# led-test.net
KiCad netlist of a schematic drawn in EAGLE
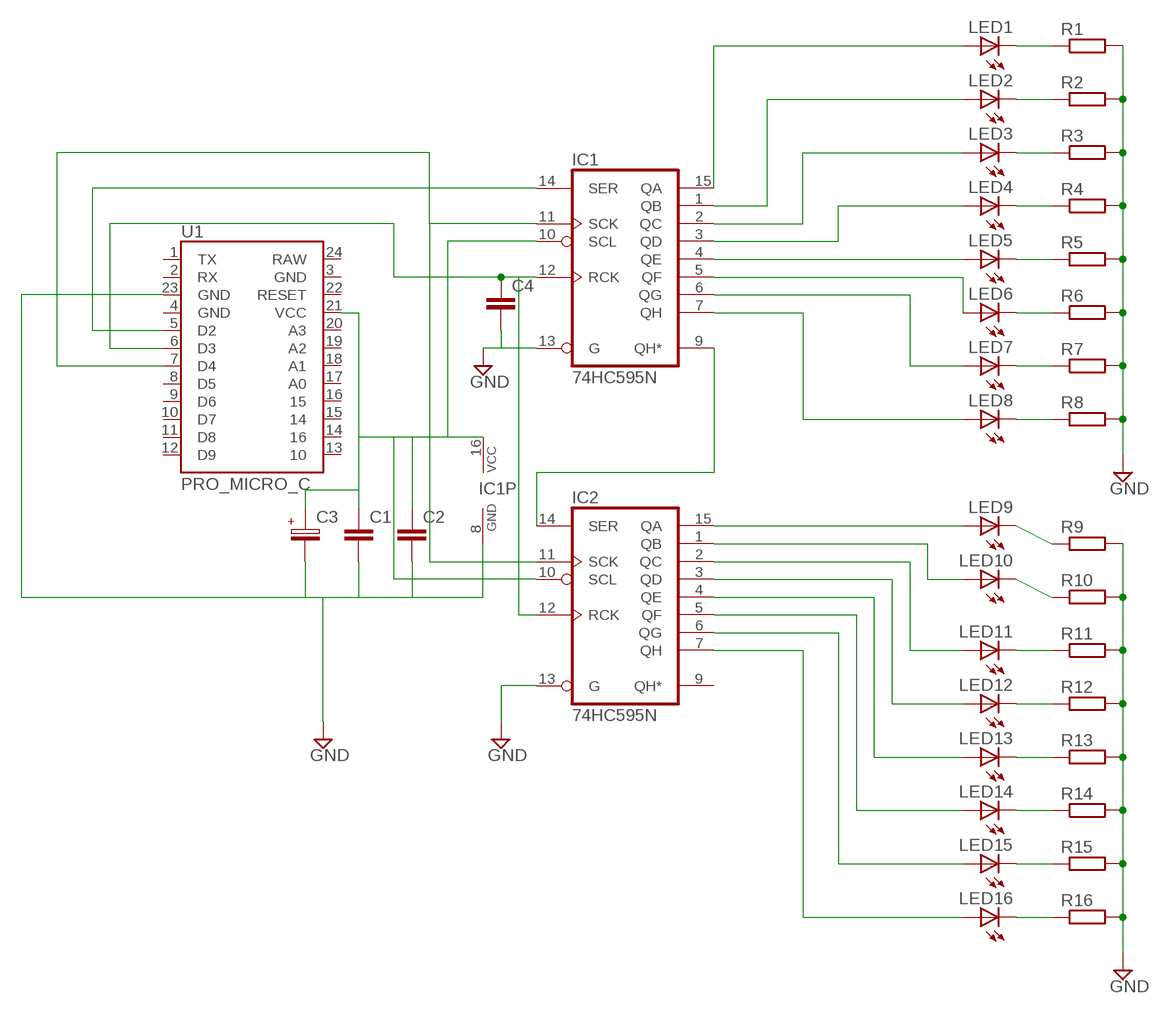
[diagram p0: schematic, sheet 1]

(export (version "E")
  (design (tool "Eeschema 10.0.6"))
  (components
    (comp (ref "C1")
      (value "072X0252")
      (footprint "eagle-import:072X025")
      (libsource (lib "eagle-import") (part "072X0252"))
    )
    (comp (ref "C2")
      (value "072X0252")
      (footprint "eagle-import:072X025")
      (libsource (lib "eagle-import") (part "072X0252"))
    )
    (comp (ref "C3")
      (value "050-EU")
      (footprint "eagle-import:050_020")
      (libsource (lib "eagle-import") (part "050-EU"))
    )
    (comp (ref "C4")
      (value "072X0252")
      (footprint "eagle-import:072X025")
      (libsource (lib "eagle-import") (part "072X0252"))
    )
    (comp (ref "IC1")
      (value "74HC595N")
      (footprint "eagle-import:DIL16")
      (libsource (lib "eagle-import") (part "74595NHC"))
    )
    (comp (ref "IC2")
      (value "74HC595N")
      (footprint "eagle-import:DIL16")
      (libsource (lib "eagle-import") (part "74595NHC"))
    )
    (comp (ref "LED1")
      (value "LED")
      (footprint "eagle-import:SMARTLED-TTW")
      (libsource (lib "eagle-import") (part "LED"))
    )
    (comp (ref "LED2")
      (value "LED")
      (footprint "eagle-import:SMARTLED-TTW")
      (libsource (lib "eagle-import") (part "LED"))
    )
    (comp (ref "LED3")
      (value "LED")
      (footprint "eagle-import:SMARTLED-TTW")
      (libsource (lib "eagle-import") (part "LED"))
    )
    (comp (ref "LED4")
      (value "LED")
      (footprint "eagle-import:SMARTLED-TTW")
      (libsource (lib "eagle-import") (part "LED"))
    )
    (comp (ref "LED5")
      (value "LED")
      (footprint "eagle-import:SMARTLED-TTW")
      (libsource (lib "eagle-import") (part "LED"))
    )
    (comp (ref "LED6")
      (value "LED")
      (footprint "eagle-import:SMARTLED-TTW")
      (libsource (lib "eagle-import") (part "LED"))
    )
    (comp (ref "LED7")
      (value "LED")
      (footprint "eagle-import:SMARTLED-TTW")
      (libsource (lib "eagle-import") (part "LED"))
    )
    (comp (ref "LED8")
      (value "LED")
      (footprint "eagle-import:SMARTLED-TTW")
      (libsource (lib "eagle-import") (part "LED"))
    )
    (comp (ref "LED9")
      (value "LED")
      (footprint "eagle-import:SMARTLED-TTW")
      (libsource (lib "eagle-import") (part "LED"))
    )
    (comp (ref "LED10")
      (value "LED")
      (footprint "eagle-import:SMARTLED-TTW")
      (libsource (lib "eagle-import") (part "LED"))
    )
    (comp (ref "LED11")
      (value "LED")
      (footprint "eagle-import:SMARTLED-TTW")
      (libsource (lib "eagle-import") (part "LED"))
    )
    (comp (ref "LED12")
      (value "LED")
      (footprint "eagle-import:SMARTLED-TTW")
      (libsource (lib "eagle-import") (part "LED"))
    )
    (comp (ref "LED13")
      (value "LED")
      (footprint "eagle-import:SMARTLED-TTW")
      (libsource (lib "eagle-import") (part "LED"))
    )
    (comp (ref "LED14")
      (value "LED")
      (footprint "eagle-import:SMARTLED-TTW")
      (libsource (lib "eagle-import") (part "LED"))
    )
    (comp (ref "LED15")
      (value "LED")
      (footprint "eagle-import:SMARTLED-TTW")
      (libsource (lib "eagle-import") (part "LED"))
    )
    (comp (ref "LED16")
      (value "LED")
      (footprint "eagle-import:SMARTLED-TTW")
      (libsource (lib "eagle-import") (part "LED"))
    )
    (comp (ref "R1")
      (value "R-EU_0204/7")
      (footprint "eagle-import:0204_7")
      (libsource (lib "eagle-import") (part "R-EU_0204/7"))
    )
    (comp (ref "R2")
      (value "R-EU_0204/7")
      (footprint "eagle-import:0204_7")
      (libsource (lib "eagle-import") (part "R-EU_0204/7"))
    )
    (comp (ref "R3")
      (value "R-EU_0204/7")
      (footprint "eagle-import:0204_7")
      (libsource (lib "eagle-import") (part "R-EU_0204/7"))
    )
    (comp (ref "R4")
      (value "R-EU_0204/7")
      (footprint "eagle-import:0204_7")
      (libsource (lib "eagle-import") (part "R-EU_0204/7"))
    )
    (comp (ref "R5")
      (value "R-EU_0204/7")
      (footprint "eagle-import:0204_7")
      (libsource (lib "eagle-import") (part "R-EU_0204/7"))
    )
    (comp (ref "R6")
      (value "R-EU_0204/7")
      (footprint "eagle-import:0204_7")
      (libsource (lib "eagle-import") (part "R-EU_0204/7"))
    )
    (comp (ref "R7")
      (value "R-EU_0204/7")
      (footprint "eagle-import:0204_7")
      (libsource (lib "eagle-import") (part "R-EU_0204/7"))
    )
    (comp (ref "R8")
      (value "R-EU_0204/7")
      (footprint "eagle-import:0204_7")
      (libsource (lib "eagle-import") (part "R-EU_0204/7"))
    )
    (comp (ref "R9")
      (value "R-EU_0204/7")
      (footprint "eagle-import:0204_7")
      (libsource (lib "eagle-import") (part "R-EU_0204/7"))
    )
    (comp (ref "R10")
      (value "R-EU_0204/7")
      (footprint "eagle-import:0204_7")
      (libsource (lib "eagle-import") (part "R-EU_0204/7"))
    )
    (comp (ref "R11")
      (value "R-EU_0204/7")
      (footprint "eagle-import:0204_7")
      (libsource (lib "eagle-import") (part "R-EU_0204/7"))
    )
    (comp (ref "R12")
      (value "R-EU_0204/7")
      (footprint "eagle-import:0204_7")
      (libsource (lib "eagle-import") (part "R-EU_0204/7"))
    )
    (comp (ref "R13")
      (value "R-EU_0204/7")
      (footprint "eagle-import:0204_7")
      (libsource (lib "eagle-import") (part "R-EU_0204/7"))
    )
    (comp (ref "R14")
      (value "R-EU_0204/7")
      (footprint "eagle-import:0204_7")
      (libsource (lib "eagle-import") (part "R-EU_0204/7"))
    )
    (comp (ref "R15")
      (value "R-EU_0204/7")
      (footprint "eagle-import:0204_7")
      (libsource (lib "eagle-import") (part "R-EU_0204/7"))
    )
    (comp (ref "R16")
      (value "R-EU_0204/7")
      (footprint "eagle-import:0204_7")
      (libsource (lib "eagle-import") (part "R-EU_0204/7"))
    )
    (comp (ref "U1")
      (value "PRO_MICRO_C")
      (footprint "eagle-import:PRO_MICRO_C")
      (libsource (lib "eagle-import") (part "PRO_MICRO_C"))
    )
  )
  (nets
    (net (code "1") (name "GND") (class "Default")
      (node (ref "C1") (pin "2") (pinfunction "2_2") (pintype "passive"))
      (node (ref "C2") (pin "2") (pinfunction "2_2") (pintype "passive"))
      (node (ref "C3") (pin "-") (pinfunction "-_-") (pintype "passive"))
      (node (ref "C4") (pin "2") (pinfunction "2_2") (pintype "passive"))
      (node (ref "IC1") (pin "13") (pinfunction "G_13") (pintype "input"))
      (node (ref "IC1") (pin "8") (pinfunction "GND_8") (pintype "power_in"))
      (node (ref "IC2") (pin "13") (pinfunction "G_13") (pintype "input"))
      (node (ref "R1") (pin "2") (pinfunction "2_2") (pintype "passive"))
      (node (ref "R10") (pin "2") (pinfunction "2_2") (pintype "passive"))
      (node (ref "R11") (pin "2") (pinfunction "2_2") (pintype "passive"))
      (node (ref "R12") (pin "2") (pinfunction "2_2") (pintype "passive"))
      (node (ref "R13") (pin "2") (pinfunction "2_2") (pintype "passive"))
      (node (ref "R14") (pin "2") (pinfunction "2_2") (pintype "passive"))
      (node (ref "R15") (pin "2") (pinfunction "2_2") (pintype "passive"))
      (node (ref "R16") (pin "2") (pinfunction "2_2") (pintype "passive"))
      (node (ref "R2") (pin "2") (pinfunction "2_2") (pintype "passive"))
      (node (ref "R3") (pin "2") (pinfunction "2_2") (pintype "passive"))
      (node (ref "R4") (pin "2") (pinfunction "2_2") (pintype "passive"))
      (node (ref "R5") (pin "2") (pinfunction "2_2") (pintype "passive"))
      (node (ref "R6") (pin "2") (pinfunction "2_2") (pintype "passive"))
      (node (ref "R7") (pin "2") (pinfunction "2_2") (pintype "passive"))
      (node (ref "R8") (pin "2") (pinfunction "2_2") (pintype "passive"))
      (node (ref "R9") (pin "2") (pinfunction "2_2") (pintype "passive"))
      (node (ref "U1") (pin "23") (pinfunction "GND_23") (pintype "bidirectional"))
    )
    (net (code "2") (name "Net-(IC1A-QA)") (class "Default")
      (node (ref "IC1") (pin "15") (pinfunction "QA_15") (pintype "tri_state"))
      (node (ref "LED1") (pin "A@1") (pinfunction "A_A@1") (pintype "passive"))
    )
    (net (code "3") (name "Net-(IC1A-QB)") (class "Default")
      (node (ref "IC1") (pin "1") (pinfunction "QB_1") (pintype "tri_state"))
      (node (ref "LED2") (pin "A@1") (pinfunction "A_A@1") (pintype "passive"))
    )
    (net (code "4") (name "Net-(IC1A-QC)") (class "Default")
      (node (ref "IC1") (pin "2") (pinfunction "QC_2") (pintype "tri_state"))
      (node (ref "LED3") (pin "A@1") (pinfunction "A_A@1") (pintype "passive"))
    )
    (net (code "5") (name "Net-(IC1A-QD)") (class "Default")
      (node (ref "IC1") (pin "3") (pinfunction "QD_3") (pintype "tri_state"))
      (node (ref "LED4") (pin "A@1") (pinfunction "A_A@1") (pintype "passive"))
    )
    (net (code "6") (name "Net-(IC1A-QE)") (class "Default")
      (node (ref "IC1") (pin "4") (pinfunction "QE_4") (pintype "tri_state"))
      (node (ref "LED5") (pin "A@1") (pinfunction "A_A@1") (pintype "passive"))
    )
    (net (code "7") (name "Net-(IC1A-QF)") (class "Default")
      (node (ref "IC1") (pin "5") (pinfunction "QF_5") (pintype "tri_state"))
      (node (ref "LED6") (pin "A@1") (pinfunction "A_A@1") (pintype "passive"))
    )
    (net (code "8") (name "Net-(IC1A-QG)") (class "Default")
      (node (ref "IC1") (pin "6") (pinfunction "QG_6") (pintype "tri_state"))
      (node (ref "LED7") (pin "A@1") (pinfunction "A_A@1") (pintype "passive"))
    )
    (net (code "9") (name "Net-(IC1A-QH)") (class "Default")
      (node (ref "IC1") (pin "7") (pinfunction "QH_7") (pintype "tri_state"))
      (node (ref "LED8") (pin "A@1") (pinfunction "A_A@1") (pintype "passive"))
    )
    (net (code "10") (name "Net-(IC1A-QH*)") (class "Default")
      (node (ref "IC1") (pin "9") (pinfunction "QH*_9") (pintype "tri_state"))
      (node (ref "IC2") (pin "14") (pinfunction "SER_14") (pintype "input"))
    )
    (net (code "11") (name "Net-(IC1A-RCK)") (class "Default")
      (node (ref "C4") (pin "1") (pinfunction "1_1") (pintype "passive"))
      (node (ref "IC1") (pin "12") (pinfunction "RCK_12") (pintype "input"))
      (node (ref "IC2") (pin "12") (pinfunction "RCK_12") (pintype "input"))
      (node (ref "U1") (pin "6") (pinfunction "D3_6") (pintype "bidirectional"))
    )
    (net (code "12") (name "Net-(IC1A-SCK)") (class "Default")
      (node (ref "IC1") (pin "11") (pinfunction "SCK_11") (pintype "input"))
      (node (ref "IC2") (pin "11") (pinfunction "SCK_11") (pintype "input"))
      (node (ref "U1") (pin "7") (pinfunction "D4_7") (pintype "bidirectional"))
    )
    (net (code "13") (name "Net-(IC1A-SCL)") (class "Default")
      (node (ref "C1") (pin "1") (pinfunction "1_1") (pintype "passive"))
      (node (ref "C2") (pin "1") (pinfunction "1_1") (pintype "passive"))
      (node (ref "C3") (pin "+") (pinfunction "+_+") (pintype "passive"))
      (node (ref "IC1") (pin "10") (pinfunction "SCL_10") (pintype "input"))
      (node (ref "IC1") (pin "16") (pinfunction "VCC_16") (pintype "power_in"))
      (node (ref "IC2") (pin "10") (pinfunction "SCL_10") (pintype "input"))
      (node (ref "U1") (pin "21") (pinfunction "VCC_21") (pintype "bidirectional"))
    )
    (net (code "14") (name "Net-(IC1A-SER)") (class "Default")
      (node (ref "IC1") (pin "14") (pinfunction "SER_14") (pintype "input"))
      (node (ref "U1") (pin "5") (pinfunction "D2_5") (pintype "bidirectional"))
    )
    (net (code "15") (name "Net-(IC2A-QA)") (class "Default")
      (node (ref "IC2") (pin "15") (pinfunction "QA_15") (pintype "tri_state"))
      (node (ref "LED9") (pin "A@1") (pinfunction "A_A@1") (pintype "passive"))
    )
    (net (code "16") (name "Net-(IC2A-QB)") (class "Default")
      (node (ref "IC2") (pin "1") (pinfunction "QB_1") (pintype "tri_state"))
      (node (ref "LED10") (pin "A@1") (pinfunction "A_A@1") (pintype "passive"))
    )
    (net (code "17") (name "Net-(IC2A-QC)") (class "Default")
      (node (ref "IC2") (pin "2") (pinfunction "QC_2") (pintype "tri_state"))
      (node (ref "LED11") (pin "A@1") (pinfunction "A_A@1") (pintype "passive"))
    )
    (net (code "18") (name "Net-(IC2A-QD)") (class "Default")
      (node (ref "IC2") (pin "3") (pinfunction "QD_3") (pintype "tri_state"))
      (node (ref "LED12") (pin "A@1") (pinfunction "A_A@1") (pintype "passive"))
    )
    (net (code "19") (name "Net-(IC2A-QE)") (class "Default")
      (node (ref "IC2") (pin "4") (pinfunction "QE_4") (pintype "tri_state"))
      (node (ref "LED13") (pin "A@1") (pinfunction "A_A@1") (pintype "passive"))
    )
    (net (code "20") (name "Net-(IC2A-QF)") (class "Default")
      (node (ref "IC2") (pin "5") (pinfunction "QF_5") (pintype "tri_state"))
      (node (ref "LED14") (pin "A@1") (pinfunction "A_A@1") (pintype "passive"))
    )
    (net (code "21") (name "Net-(IC2A-QG)") (class "Default")
      (node (ref "IC2") (pin "6") (pinfunction "QG_6") (pintype "tri_state"))
      (node (ref "LED15") (pin "A@1") (pinfunction "A_A@1") (pintype "passive"))
    )
    (net (code "22") (name "Net-(IC2A-QH)") (class "Default")
      (node (ref "IC2") (pin "7") (pinfunction "QH_7") (pintype "tri_state"))
      (node (ref "LED16") (pin "A@1") (pinfunction "A_A@1") (pintype "passive"))
    )
    (net (code "23") (name "Net-(LED1-C)") (class "Default")
      (node (ref "LED1") (pin "C@1") (pinfunction "C_C@1") (pintype "passive"))
      (node (ref "R1") (pin "1") (pinfunction "1_1") (pintype "passive"))
    )
    (net (code "24") (name "Net-(LED2-C)") (class "Default")
      (node (ref "LED2") (pin "C@1") (pinfunction "C_C@1") (pintype "passive"))
      (node (ref "R2") (pin "1") (pinfunction "1_1") (pintype "passive"))
    )
    (net (code "25") (name "Net-(LED3-C)") (class "Default")
      (node (ref "LED3") (pin "C@1") (pinfunction "C_C@1") (pintype "passive"))
      (node (ref "R3") (pin "1") (pinfunction "1_1") (pintype "passive"))
    )
    (net (code "26") (name "Net-(LED4-C)") (class "Default")
      (node (ref "LED4") (pin "C@1") (pinfunction "C_C@1") (pintype "passive"))
      (node (ref "R4") (pin "1") (pinfunction "1_1") (pintype "passive"))
    )
    (net (code "27") (name "Net-(LED5-C)") (class "Default")
      (node (ref "LED5") (pin "C@1") (pinfunction "C_C@1") (pintype "passive"))
      (node (ref "R5") (pin "1") (pinfunction "1_1") (pintype "passive"))
    )
    (net (code "28") (name "Net-(LED6-C)") (class "Default")
      (node (ref "LED6") (pin "C@1") (pinfunction "C_C@1") (pintype "passive"))
      (node (ref "R6") (pin "1") (pinfunction "1_1") (pintype "passive"))
    )
    (net (code "29") (name "Net-(LED7-C)") (class "Default")
      (node (ref "LED7") (pin "C@1") (pinfunction "C_C@1") (pintype "passive"))
      (node (ref "R7") (pin "1") (pinfunction "1_1") (pintype "passive"))
    )
    (net (code "30") (name "Net-(LED8-C)") (class "Default")
      (node (ref "LED8") (pin "C@1") (pinfunction "C_C@1") (pintype "passive"))
      (node (ref "R8") (pin "1") (pinfunction "1_1") (pintype "passive"))
    )
    (net (code "31") (name "Net-(LED9-C)") (class "Default")
      (node (ref "LED9") (pin "C@1") (pinfunction "C_C@1") (pintype "passive"))
      (node (ref "R9") (pin "1") (pinfunction "1_1") (pintype "passive"))
    )
    (net (code "32") (name "Net-(LED10-C)") (class "Default")
      (node (ref "LED10") (pin "C@1") (pinfunction "C_C@1") (pintype "passive"))
      (node (ref "R10") (pin "1") (pinfunction "1_1") (pintype "passive"))
    )
    (net (code "33") (name "Net-(LED11-C)") (class "Default")
      (node (ref "LED11") (pin "C@1") (pinfunction "C_C@1") (pintype "passive"))
      (node (ref "R11") (pin "1") (pinfunction "1_1") (pintype "passive"))
    )
    (net (code "34") (name "Net-(LED12-C)") (class "Default")
      (node (ref "LED12") (pin "C@1") (pinfunction "C_C@1") (pintype "passive"))
      (node (ref "R12") (pin "1") (pinfunction "1_1") (pintype "passive"))
    )
    (net (code "35") (name "Net-(LED13-C)") (class "Default")
      (node (ref "LED13") (pin "C@1") (pinfunction "C_C@1") (pintype "passive"))
      (node (ref "R13") (pin "1") (pinfunction "1_1") (pintype "passive"))
    )
    (net (code "36") (name "Net-(LED14-C)") (class "Default")
      (node (ref "LED14") (pin "C@1") (pinfunction "C_C@1") (pintype "passive"))
      (node (ref "R14") (pin "1") (pinfunction "1_1") (pintype "passive"))
    )
    (net (code "37") (name "Net-(LED15-C)") (class "Default")
      (node (ref "LED15") (pin "C@1") (pinfunction "C_C@1") (pintype "passive"))
      (node (ref "R15") (pin "1") (pinfunction "1_1") (pintype "passive"))
    )
    (net (code "38") (name "Net-(LED16-C)") (class "Default")
      (node (ref "LED16") (pin "C@1") (pinfunction "C_C@1") (pintype "passive"))
      (node (ref "R16") (pin "1") (pinfunction "1_1") (pintype "passive"))
    )
    (net (code "39") (name "unconnected-(IC2A-QH*-Pad9)") (class "Default")
      (node (ref "IC2") (pin "9") (pinfunction "QH*_9") (pintype "tri_state"))
    )
    (net (code "40") (name "unconnected-(U1-10-Pad13)") (class "Default")
      (node (ref "U1") (pin "13") (pinfunction "10_13") (pintype "bidirectional"))
    )
    (net (code "41") (name "unconnected-(U1-14-Pad15)") (class "Default")
      (node (ref "U1") (pin "15") (pinfunction "14_15") (pintype "bidirectional"))
    )
    (net (code "42") (name "unconnected-(U1-15-Pad16)") (class "Default")
      (node (ref "U1") (pin "16") (pinfunction "15_16") (pintype "bidirectional"))
    )
    (net (code "43") (name "unconnected-(U1-16-Pad14)") (class "Default")
      (node (ref "U1") (pin "14") (pinfunction "16_14") (pintype "bidirectional"))
    )
    (net (code "44") (name "unconnected-(U1-A0-Pad17)") (class "Default")
      (node (ref "U1") (pin "17") (pinfunction "A0_17") (pintype "bidirectional"))
    )
    (net (code "45") (name "unconnected-(U1-A1-Pad18)") (class "Default")
      (node (ref "U1") (pin "18") (pinfunction "A1_18") (pintype "bidirectional"))
    )
    (net (code "46") (name "unconnected-(U1-A2-Pad19)") (class "Default")
      (node (ref "U1") (pin "19") (pinfunction "A2_19") (pintype "bidirectional"))
    )
    (net (code "47") (name "unconnected-(U1-A3-Pad20)") (class "Default")
      (node (ref "U1") (pin "20") (pinfunction "A3_20") (pintype "bidirectional"))
    )
    (net (code "48") (name "unconnected-(U1-D5-Pad8)") (class "Default")
      (node (ref "U1") (pin "8") (pinfunction "D5_8") (pintype "bidirectional"))
    )
    (net (code "49") (name "unconnected-(U1-D6-Pad9)") (class "Default")
      (node (ref "U1") (pin "9") (pinfunction "D6_9") (pintype "bidirectional"))
    )
    (net (code "50") (name "unconnected-(U1-D7-Pad10)") (class "Default")
      (node (ref "U1") (pin "10") (pinfunction "D7_10") (pintype "bidirectional"))
    )
    (net (code "51") (name "unconnected-(U1-D8-Pad11)") (class "Default")
      (node (ref "U1") (pin "11") (pinfunction "D8_11") (pintype "bidirectional"))
    )
    (net (code "52") (name "unconnected-(U1-D9-Pad12)") (class "Default")
      (node (ref "U1") (pin "12") (pinfunction "D9_12") (pintype "bidirectional"))
    )
    (net (code "53") (name "unconnected-(U1-GND-Pad3)") (class "Default")
      (node (ref "U1") (pin "3") (pinfunction "GND_3") (pintype "bidirectional"))
    )
    (net (code "54") (name "unconnected-(U1-GND-Pad4)") (class "Default")
      (node (ref "U1") (pin "4") (pinfunction "GND_4") (pintype "bidirectional"))
    )
    (net (code "55") (name "unconnected-(U1-RAW-Pad24)") (class "Default")
      (node (ref "U1") (pin "24") (pinfunction "RAW_24") (pintype "bidirectional"))
    )
    (net (code "56") (name "unconnected-(U1-RESET-Pad22)") (class "Default")
      (node (ref "U1") (pin "22") (pinfunction "RESET_22") (pintype "bidirectional"))
    )
    (net (code "57") (name "unconnected-(U1-RX-Pad2)") (class "Default")
      (node (ref "U1") (pin "2") (pinfunction "RX_2") (pintype "bidirectional"))
    )
    (net (code "58") (name "unconnected-(U1-TX-Pad1)") (class "Default")
      (node (ref "U1") (pin "1") (pinfunction "TX_1") (pintype "bidirectional"))
    )
  )
)
